# rs485.net
KiCad netlist of a schematic drawn in Altium Designer
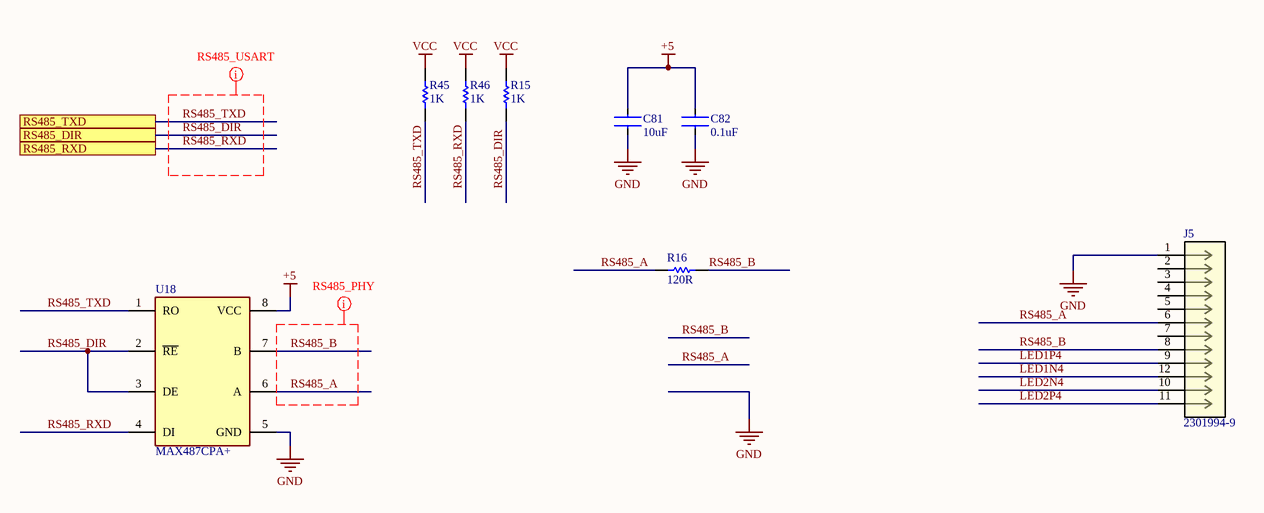
[diagram p0: rs485.SchDoc]

(export (version "E")
  (design (tool "Eeschema 10.0.6"))
  (components
    (comp (ref "C81")
      (value "10uF")
      (footprint "C0402")
      (description "Cap Ceramic 10uF 16V X7R 10% Pad SMD 1206 125°C T/R")
      (fields
        (field (name "MANUFACTURER") "Samsung")
        (field (name "MANUFACTURER PART NUMBER") "CL31B106KOHNNNE")
      )
      (libsource (lib "afra") (part "CL31B106KOHNNNE"))
    )
    (comp (ref "C82")
      (value "0.1uF")
      (footprint "C0402")
      (description "Ceramic capacitor SMD-1206 100nF /50V X7R# K +-10%, Samsung, RoHS")
      (fields
        (field (name "MANUFACTURER") "Samsung")
        (field (name "MANUFACTURER PART NUMBER") "CL31B104KBCNNNC")
      )
      (libsource (lib "afra") (part "CL31B104KBCNNNC"))
    )
    (comp (ref "J5")
      (value "2301994-9")
      (footprint "CONN12_2301994-9_TEC")
      (description "No Description Available")
      (fields (field (name "COPYRIGHT") "Copyright (C) 2022 Ultra Librarian. All rights reserved."))
      (libsource (lib "afra") (part "2301994-9"))
    )
    (comp (ref "R15")
      (value "1K")
      (footprint "R0402")
      (description "In a Pack of 5000, 1K 1206 Thick Film SMD Resistor ±1% 0.25W - RC1206FR-071KL")
      (fields
        (field (name "MANUFACTURER") "Yageo")
        (field (name "MANUFACTURER PART NUMBER") "RC1206FR-071KL")
      )
      (libsource (lib "afra") (part "RC1206FR-071KL"))
    )
    (comp (ref "R16")
      (value "120R")
      (footprint "R0402")
      (description "Res Thick Film 1206 120 Ohm 1% 0.25W(1/4W) ±100ppm/°C Pad SMD T/R")
      (fields
        (field (name "MANUFACTURER") "Yageo")
        (field (name "MANUFACTURER PART NUMBER") "RC1206FR-07120RL")
      )
      (libsource (lib "afra") (part "RC1206FR-07120RL"))
    )
    (comp (ref "R45")
      (value "1K")
      (footprint "R0402")
      (description "In a Pack of 5000, 1K 1206 Thick Film SMD Resistor ±1% 0.25W - RC1206FR-071KL")
      (fields
        (field (name "MANUFACTURER") "Yageo")
        (field (name "MANUFACTURER PART NUMBER") "RC1206FR-071KL")
      )
      (libsource (lib "afra") (part "RC1206FR-071KL"))
    )
    (comp (ref "R46")
      (value "1K")
      (footprint "R0402")
      (description "In a Pack of 5000, 1K 1206 Thick Film SMD Resistor ±1% 0.25W - RC1206FR-071KL")
      (fields
        (field (name "MANUFACTURER") "Yageo")
        (field (name "MANUFACTURER PART NUMBER") "RC1206FR-071KL")
      )
      (libsource (lib "afra") (part "RC1206FR-071KL"))
    )
    (comp (ref "U18")
      (value "MAX487CPA+")
      (footprint "SOIC-8")
      (description "Interface IC RS422/485 DIL-8, MAX487ECPA+, Maxim")
      (fields (field (name "MANUFACTURER") "Maxim") (field (name "MANUFACTURER PART NUMBER") "MAX487ECPA+"))
      (libsource (lib "afra") (part "MAX487ECPA+"))
    )
  )
  (nets
    (net (code "1") (name "+5") (class "Default")
      (node (ref "C81") (pin "1") (pinfunction "1_1") (pintype "passive"))
      (node (ref "C82") (pin "1") (pinfunction "1_1") (pintype "passive"))
      (node (ref "U18") (pin "8") (pinfunction "VCC_8") (pintype "passive"))
    )
    (net (code "2") (name "/LED1N4") (class "Default")
      (node (ref "J5") (pin "12") (pinfunction "12_12") (pintype "passive"))
    )
    (net (code "3") (name "/LED1P4") (class "Default")
      (node (ref "J5") (pin "9") (pinfunction "9_9") (pintype "passive"))
    )
    (net (code "4") (name "/LED2N4") (class "Default")
      (node (ref "J5") (pin "10") (pinfunction "10_10") (pintype "passive"))
    )
    (net (code "5") (name "/LED2P4") (class "Default")
      (node (ref "J5") (pin "11") (pinfunction "11_11") (pintype "passive"))
    )
    (net (code "6") (name "/RS485_A") (class "Default")
      (node (ref "J5") (pin "6") (pinfunction "6_6") (pintype "passive"))
      (node (ref "R16") (pin "1") (pinfunction "1_1") (pintype "passive"))
      (node (ref "U18") (pin "6") (pinfunction "A_6") (pintype "passive"))
    )
    (net (code "7") (name "/RS485_B") (class "Default")
      (node (ref "J5") (pin "8") (pinfunction "8_8") (pintype "passive"))
      (node (ref "R16") (pin "2") (pinfunction "2_2") (pintype "passive"))
      (node (ref "U18") (pin "7") (pinfunction "B_7") (pintype "passive"))
    )
    (net (code "8") (name "/RS485_DIR") (class "Default")
      (node (ref "R15") (pin "1") (pinfunction "1_1") (pintype "passive"))
      (node (ref "U18") (pin "2") (pinfunction "~{RE}_2") (pintype "passive"))
      (node (ref "U18") (pin "3") (pinfunction "DE_3") (pintype "passive"))
    )
    (net (code "9") (name "/RS485_RXD") (class "Default")
      (node (ref "R46") (pin "1") (pinfunction "1_1") (pintype "passive"))
      (node (ref "U18") (pin "4") (pinfunction "DI_4") (pintype "passive"))
    )
    (net (code "10") (name "/RS485_TXD") (class "Default")
      (node (ref "R45") (pin "1") (pinfunction "1_1") (pintype "passive"))
      (node (ref "U18") (pin "1") (pinfunction "RO_1") (pintype "passive"))
    )
    (net (code "11") (name "GND") (class "Default")
      (node (ref "C81") (pin "2") (pinfunction "2_2") (pintype "passive"))
      (node (ref "C82") (pin "2") (pinfunction "2_2") (pintype "passive"))
      (node (ref "J5") (pin "1") (pinfunction "1_1") (pintype "passive"))
      (node (ref "U18") (pin "5") (pinfunction "GND_5") (pintype "passive"))
    )
    (net (code "12") (name "VCC") (class "Default")
      (node (ref "R15") (pin "2") (pinfunction "2_2") (pintype "passive"))
      (node (ref "R45") (pin "2") (pinfunction "2_2") (pintype "passive"))
      (node (ref "R46") (pin "2") (pinfunction "2_2") (pintype "passive"))
    )
    (net (code "13") (name "unconnected-(J5-Pad2)") (class "Default")
      (node (ref "J5") (pin "2") (pinfunction "2_2") (pintype "passive"))
    )
    (net (code "14") (name "unconnected-(J5-Pad3)") (class "Default")
      (node (ref "J5") (pin "3") (pinfunction "3_3") (pintype "passive"))
    )
    (net (code "15") (name "unconnected-(J5-Pad4)") (class "Default")
      (node (ref "J5") (pin "4") (pinfunction "4_4") (pintype "passive"))
    )
    (net (code "16") (name "unconnected-(J5-Pad5)") (class "Default")
      (node (ref "J5") (pin "5") (pinfunction "5_5") (pintype "passive"))
    )
    (net (code "17") (name "unconnected-(J5-Pad7)") (class "Default")
      (node (ref "J5") (pin "7") (pinfunction "7_7") (pintype "passive"))
    )
  )
)
